# FPGA_PWR.net
KiCad netlist of a schematic drawn in Altium Designer
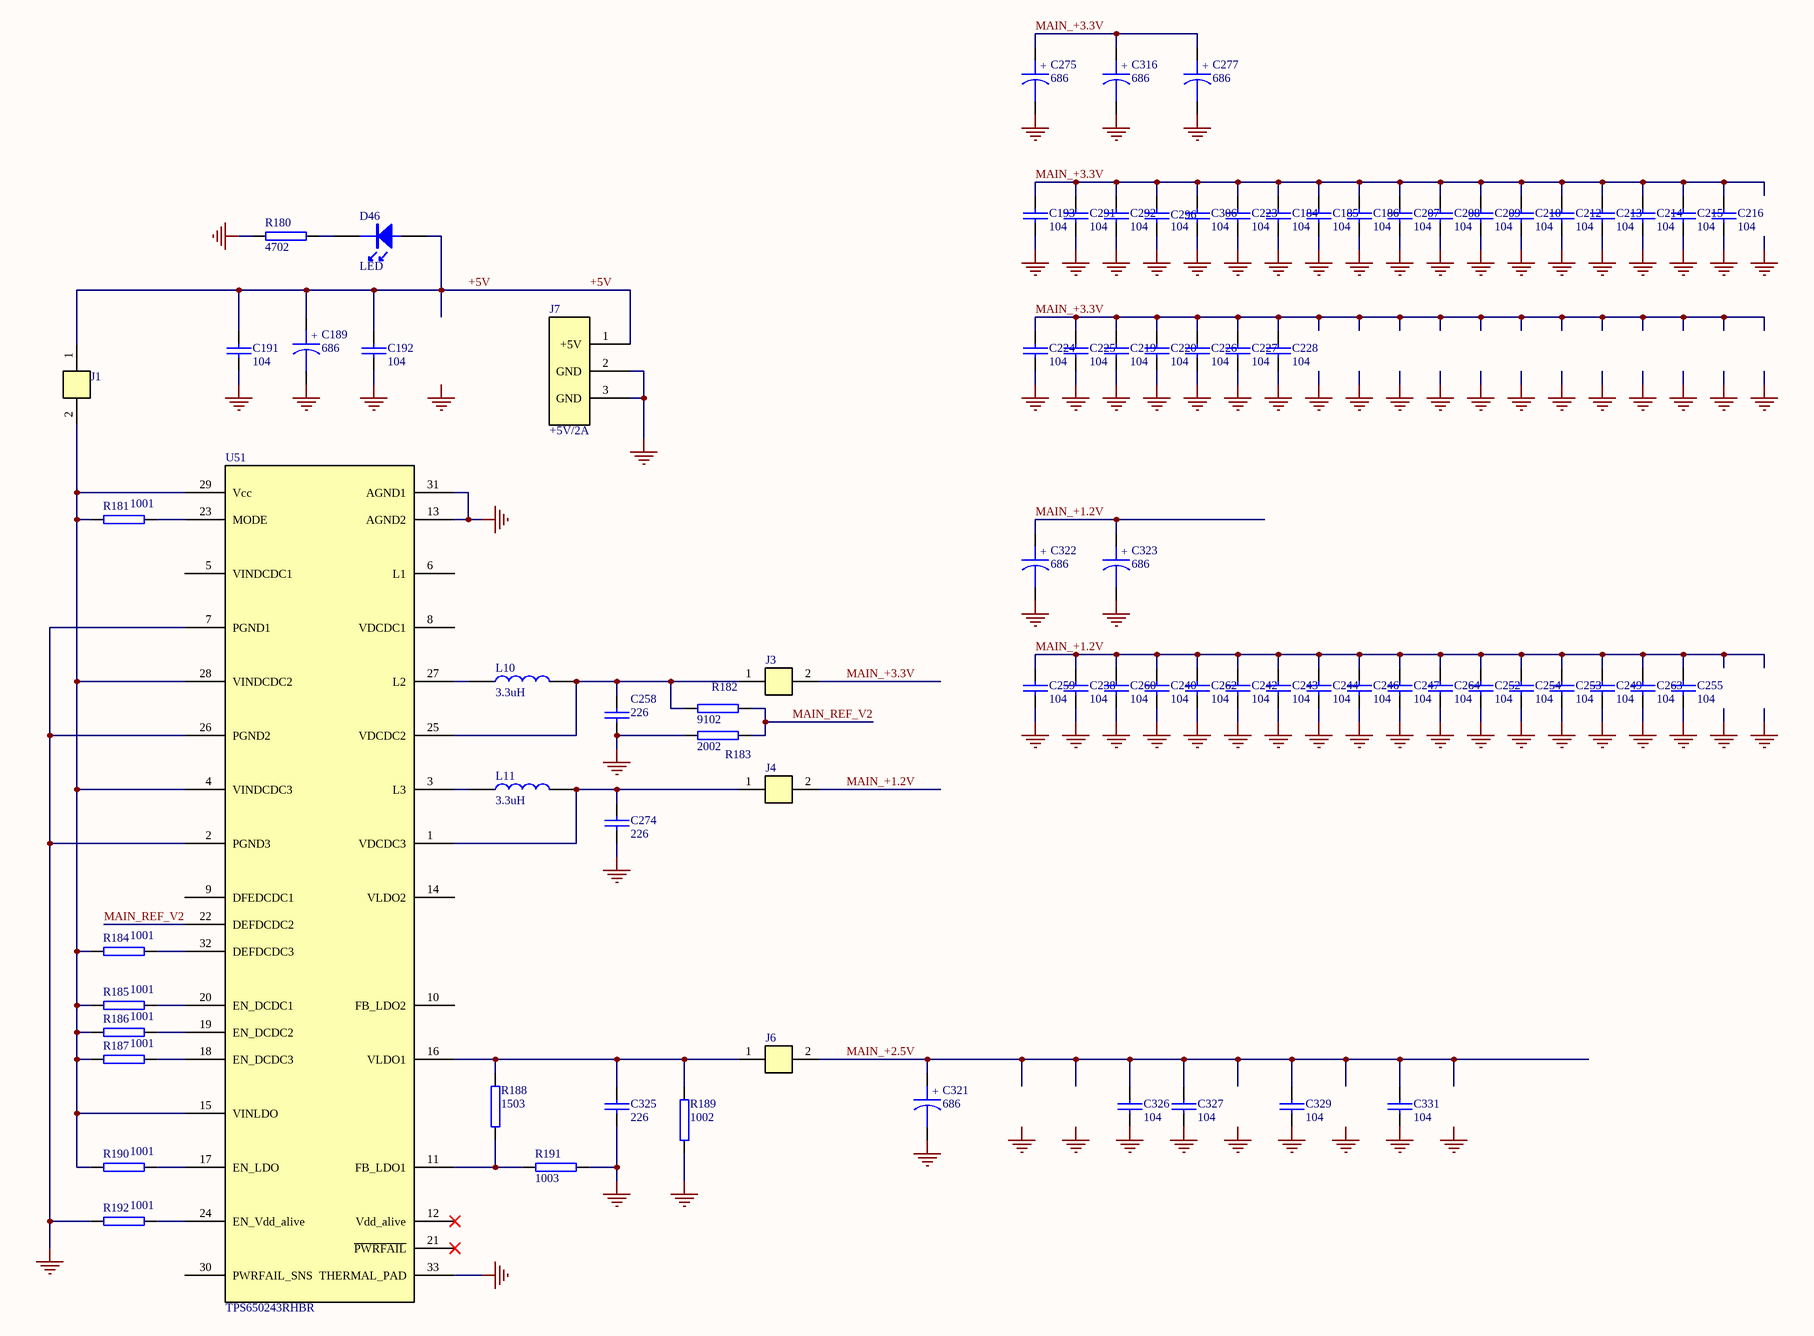
[diagram p0: FPGA_PWR.SchDoc]

(export (version "E")
  (design (tool "Eeschema 10.0.6"))
  (components
    (comp (ref "C184")
      (value "104")
      (footprint "0402C")
      (description "Capacitor")
      (libsource (lib "*") (part "CAP"))
    )
    (comp (ref "C185")
      (value "104")
      (footprint "0402C")
      (description "Capacitor")
      (libsource (lib "*") (part "CAP"))
    )
    (comp (ref "C186")
      (value "104")
      (footprint "0402C")
      (description "Capacitor")
      (libsource (lib "*") (part "CAP"))
    )
    (comp (ref "C189")
      (value "686")
      (footprint "6032")
      (description "Capacitor")
      (libsource (lib "*") (part "CAPACITOR POL"))
    )
    (comp (ref "C191")
      (value "104")
      (footprint "0805C")
      (description "Capacitor")
      (libsource (lib "*") (part "CAP"))
    )
    (comp (ref "C192")
      (value "104")
      (footprint "0805C")
      (description "Capacitor")
      (libsource (lib "*") (part "CAP"))
    )
    (comp (ref "C193")
      (value "104")
      (footprint "0805-104")
      (description "Capacitor")
      (libsource (lib "*") (part "CAP"))
    )
    (comp (ref "C207")
      (value "104")
      (footprint "0402C")
      (description "Capacitor")
      (libsource (lib "*") (part "CAP"))
    )
    (comp (ref "C208")
      (value "104")
      (footprint "0402C")
      (description "Capacitor")
      (libsource (lib "*") (part "CAP"))
    )
    (comp (ref "C209")
      (value "104")
      (footprint "0402C")
      (description "Capacitor")
      (libsource (lib "*") (part "CAP"))
    )
    (comp (ref "C210")
      (value "104")
      (footprint "0402C")
      (description "Capacitor")
      (libsource (lib "*") (part "CAP"))
    )
    (comp (ref "C212")
      (value "104")
      (footprint "0402C")
      (description "Capacitor")
      (libsource (lib "*") (part "CAP"))
    )
    (comp (ref "C213")
      (value "104")
      (footprint "0402C")
      (description "Capacitor")
      (libsource (lib "*") (part "CAP"))
    )
    (comp (ref "C214")
      (value "104")
      (footprint "0402C")
      (description "Capacitor")
      (libsource (lib "*") (part "CAP"))
    )
    (comp (ref "C215")
      (value "104")
      (footprint "0402C")
      (description "Capacitor")
      (libsource (lib "*") (part "CAP"))
    )
    (comp (ref "C216")
      (value "104")
      (footprint "0402C")
      (description "Capacitor")
      (libsource (lib "*") (part "CAP"))
    )
    (comp (ref "C219")
      (value "104")
      (footprint "0402C")
      (description "Capacitor")
      (libsource (lib "*") (part "CAP"))
    )
    (comp (ref "C220")
      (value "104")
      (footprint "0402C")
      (description "Capacitor")
      (libsource (lib "*") (part "CAP"))
    )
    (comp (ref "C223")
      (value "104")
      (footprint "0402C")
      (description "Capacitor")
      (libsource (lib "*") (part "CAP"))
    )
    (comp (ref "C224")
      (value "104")
      (footprint "0402C")
      (description "Capacitor")
      (libsource (lib "*") (part "CAP"))
    )
    (comp (ref "C225")
      (value "104")
      (footprint "0402C")
      (description "Capacitor")
      (libsource (lib "*") (part "CAP"))
    )
    (comp (ref "C226")
      (value "104")
      (footprint "0402C")
      (description "Capacitor")
      (libsource (lib "*") (part "CAP"))
    )
    (comp (ref "C227")
      (value "104")
      (footprint "0402C")
      (description "Capacitor")
      (libsource (lib "*") (part "CAP"))
    )
    (comp (ref "C228")
      (value "104")
      (footprint "0402C")
      (description "Capacitor")
      (libsource (lib "*") (part "CAP"))
    )
    (comp (ref "C238")
      (value "104")
      (footprint "0402C")
      (description "Capacitor")
      (libsource (lib "*") (part "CAP"))
    )
    (comp (ref "C240")
      (value "104")
      (footprint "0805-104")
      (description "Capacitor")
      (libsource (lib "*") (part "CAP"))
    )
    (comp (ref "C242")
      (value "104")
      (footprint "0402C")
      (description "Capacitor")
      (libsource (lib "*") (part "CAP"))
    )
    (comp (ref "C243")
      (value "104")
      (footprint "0402C")
      (description "Capacitor")
      (libsource (lib "*") (part "CAP"))
    )
    (comp (ref "C244")
      (value "104")
      (footprint "0402C")
      (description "Capacitor")
      (libsource (lib "*") (part "CAP"))
    )
    (comp (ref "C246")
      (value "104")
      (footprint "0402C")
      (description "Capacitor")
      (libsource (lib "*") (part "CAP"))
    )
    (comp (ref "C247")
      (value "104")
      (footprint "0402C")
      (description "Capacitor")
      (libsource (lib "*") (part "CAP"))
    )
    (comp (ref "C249")
      (value "104")
      (footprint "0402C")
      (description "Capacitor")
      (libsource (lib "*") (part "CAP"))
    )
    (comp (ref "C252")
      (value "104")
      (footprint "0402C")
      (description "Capacitor")
      (libsource (lib "*") (part "CAP"))
    )
    (comp (ref "C253")
      (value "104")
      (footprint "0402C")
      (description "Capacitor")
      (libsource (lib "*") (part "CAP"))
    )
    (comp (ref "C254")
      (value "104")
      (footprint "0402C")
      (description "Capacitor")
      (libsource (lib "*") (part "CAP"))
    )
    (comp (ref "C255")
      (value "104")
      (footprint "0805-104")
      (description "Capacitor")
      (libsource (lib "*") (part "CAP"))
    )
    (comp (ref "C258")
      (value "226")
      (footprint "C226")
      (description "Capacitor")
      (libsource (lib "*") (part "CAP"))
    )
    (comp (ref "C259")
      (value "104")
      (footprint "0402C")
      (description "Capacitor")
      (libsource (lib "*") (part "CAP"))
    )
    (comp (ref "C260")
      (value "104")
      (footprint "0402C")
      (description "Capacitor")
      (libsource (lib "*") (part "CAP"))
    )
    (comp (ref "C262")
      (value "104")
      (footprint "0402C")
      (description "Capacitor")
      (libsource (lib "*") (part "CAP"))
    )
    (comp (ref "C263")
      (value "104")
      (footprint "0402C")
      (description "Capacitor")
      (libsource (lib "*") (part "CAP"))
    )
    (comp (ref "C264")
      (value "104")
      (footprint "0402C")
      (description "Capacitor")
      (libsource (lib "*") (part "CAP"))
    )
    (comp (ref "C274")
      (value "226")
      (footprint "C226")
      (description "Capacitor")
      (libsource (lib "*") (part "CAP"))
    )
    (comp (ref "C275")
      (value "686")
      (footprint "6032")
      (description "Capacitor")
      (libsource (lib "*") (part "CAPACITOR POL"))
    )
    (comp (ref "C277")
      (value "686")
      (footprint "6032")
      (description "Capacitor")
      (libsource (lib "*") (part "CAPACITOR POL"))
    )
    (comp (ref "C291")
      (value "104")
      (footprint "0402C")
      (description "Capacitor")
      (libsource (lib "*") (part "CAP"))
    )
    (comp (ref "C292")
      (value "104")
      (footprint "0402C")
      (description "Capacitor")
      (libsource (lib "*") (part "CAP"))
    )
    (comp (ref "C296")
      (value "104")
      (footprint "0805C")
      (description "Capacitor")
      (libsource (lib "*") (part "CAP"))
    )
    (comp (ref "C306")
      (value "104")
      (footprint "0402C")
      (description "Capacitor")
      (libsource (lib "*") (part "CAP"))
    )
    (comp (ref "C316")
      (value "686")
      (footprint "6032")
      (description "Capacitor")
      (libsource (lib "*") (part "CAPACITOR POL"))
    )
    (comp (ref "C321")
      (value "686")
      (footprint "6032")
      (description "Capacitor")
      (libsource (lib "*") (part "CAPACITOR POL"))
    )
    (comp (ref "C322")
      (value "686")
      (footprint "6032")
      (description "Capacitor")
      (libsource (lib "*") (part "CAPACITOR POL"))
    )
    (comp (ref "C323")
      (value "686")
      (footprint "6032")
      (description "Capacitor")
      (libsource (lib "*") (part "CAPACITOR POL"))
    )
    (comp (ref "C325")
      (value "226")
      (footprint "C226")
      (description "Capacitor")
      (libsource (lib "*") (part "CAP"))
    )
    (comp (ref "C326")
      (value "104")
      (footprint "0402C")
      (description "Capacitor")
      (libsource (lib "*") (part "CAP"))
    )
    (comp (ref "C327")
      (value "104")
      (footprint "0402C")
      (description "Capacitor")
      (libsource (lib "*") (part "CAP"))
    )
    (comp (ref "C329")
      (value "104")
      (footprint "0402C")
      (description "Capacitor")
      (libsource (lib "*") (part "CAP"))
    )
    (comp (ref "C331")
      (value "104")
      (footprint "0402C")
      (description "Capacitor")
      (libsource (lib "*") (part "CAP"))
    )
    (comp (ref "D46") (value "LED") (footprint "0805_LED") (libsource (lib "*") (part "LED")))
    (comp (ref "J1") (value "~") (footprint "I_ON") (libsource (lib "") (part "I_ON_1")))
    (comp (ref "J3") (value "~") (footprint "I_ON") (libsource (lib "*") (part "I_ON")))
    (comp (ref "J4") (value "~") (footprint "I_ON") (libsource (lib "*") (part "I_ON")))
    (comp (ref "J6") (value "~") (footprint "I_ON") (libsource (lib "*") (part "I_ON")))
    (comp (ref "J7") (value "+5V/2A") (footprint "POW") (libsource (lib "*") (part "POW")))
    (comp (ref "L10") (value "3.3uH") (footprint "L3R3") (libsource (lib "*") (part "L")))
    (comp (ref "L11") (value "3.3uH") (footprint "L3R3") (libsource (lib "*") (part "L")))
    (comp (ref "R180") (value "4702") (footprint "0805R") (libsource (lib "*") (part "RES2")))
    (comp (ref "R181") (value "1001") (footprint "0805R") (libsource (lib "*") (part "RES2")))
    (comp (ref "R182") (value "9102") (footprint "0805") (libsource (lib "*") (part "RES2")))
    (comp (ref "R183") (value "2002") (footprint "0805") (libsource (lib "*") (part "RES2")))
    (comp (ref "R184") (value "1001") (footprint "0805") (libsource (lib "*") (part "RES2")))
    (comp (ref "R185") (value "1001") (footprint "0805") (libsource (lib "*") (part "RES2")))
    (comp (ref "R186") (value "1001") (footprint "0805") (libsource (lib "*") (part "RES2")))
    (comp (ref "R187") (value "1001") (footprint "0805") (libsource (lib "*") (part "RES2")))
    (comp (ref "R188") (value "1503") (footprint "0805") (libsource (lib "*") (part "RES2")))
    (comp (ref "R189") (value "1002") (footprint "0805") (libsource (lib "") (part "RES2_1")))
    (comp (ref "R190") (value "1001") (footprint "0805") (libsource (lib "*") (part "RES2")))
    (comp (ref "R191") (value "1003") (footprint "0805") (libsource (lib "*") (part "RES2")))
    (comp (ref "R192") (value "1001") (footprint "0805") (libsource (lib "*") (part "RES2")))
    (comp (ref "U51") (value "TPS650243RHBR") (footprint "VQFN32") (libsource (lib "*") (part "TPS650243")))
  )
  (nets
    (net (code "1") (name "/+5V") (class "Default")
      (node (ref "C189") (pin "1") (pinfunction "1_1") (pintype "passive"))
      (node (ref "C191") (pin "2") (pinfunction "2_2") (pintype "passive"))
      (node (ref "C192") (pin "2") (pinfunction "2_2") (pintype "passive"))
      (node (ref "D46") (pin "1") (pinfunction "A_1") (pintype "passive"))
      (node (ref "J1") (pin "1") (pintype "passive"))
      (node (ref "J7") (pin "1") (pinfunction "+5V_1") (pintype "passive"))
    )
    (net (code "2") (name "/MAIN_+1.2V") (class "Default")
      (node (ref "C238") (pin "2") (pinfunction "2_2") (pintype "passive"))
      (node (ref "C240") (pin "2") (pinfunction "2_2") (pintype "passive"))
      (node (ref "C242") (pin "2") (pinfunction "2_2") (pintype "passive"))
      (node (ref "C243") (pin "2") (pinfunction "2_2") (pintype "passive"))
      (node (ref "C244") (pin "2") (pinfunction "2_2") (pintype "passive"))
      (node (ref "C246") (pin "2") (pinfunction "2_2") (pintype "passive"))
      (node (ref "C247") (pin "2") (pinfunction "2_2") (pintype "passive"))
      (node (ref "C249") (pin "2") (pinfunction "2_2") (pintype "passive"))
      (node (ref "C252") (pin "2") (pinfunction "2_2") (pintype "passive"))
      (node (ref "C253") (pin "2") (pinfunction "2_2") (pintype "passive"))
      (node (ref "C254") (pin "2") (pinfunction "2_2") (pintype "passive"))
      (node (ref "C255") (pin "2") (pinfunction "2_2") (pintype "passive"))
      (node (ref "C259") (pin "2") (pinfunction "2_2") (pintype "passive"))
      (node (ref "C260") (pin "2") (pinfunction "2_2") (pintype "passive"))
      (node (ref "C262") (pin "2") (pinfunction "2_2") (pintype "passive"))
      (node (ref "C263") (pin "2") (pinfunction "2_2") (pintype "passive"))
      (node (ref "C264") (pin "2") (pinfunction "2_2") (pintype "passive"))
      (node (ref "C322") (pin "1") (pinfunction "1_1") (pintype "passive"))
      (node (ref "C323") (pin "1") (pinfunction "1_1") (pintype "passive"))
      (node (ref "J4") (pin "2") (pintype "passive"))
    )
    (net (code "3") (name "/MAIN_+2.5V") (class "Default")
      (node (ref "C321") (pin "1") (pinfunction "1_1") (pintype "passive"))
      (node (ref "C326") (pin "2") (pinfunction "2_2") (pintype "passive"))
      (node (ref "C327") (pin "2") (pinfunction "2_2") (pintype "passive"))
      (node (ref "C329") (pin "2") (pinfunction "2_2") (pintype "passive"))
      (node (ref "C331") (pin "2") (pinfunction "2_2") (pintype "passive"))
      (node (ref "J6") (pin "2") (pintype "passive"))
    )
    (net (code "4") (name "/MAIN_+3.3V") (class "Default")
      (node (ref "C184") (pin "2") (pinfunction "2_2") (pintype "passive"))
      (node (ref "C185") (pin "2") (pinfunction "2_2") (pintype "passive"))
      (node (ref "C186") (pin "2") (pinfunction "2_2") (pintype "passive"))
      (node (ref "C193") (pin "2") (pinfunction "2_2") (pintype "passive"))
      (node (ref "C207") (pin "2") (pinfunction "2_2") (pintype "passive"))
      (node (ref "C208") (pin "2") (pinfunction "2_2") (pintype "passive"))
      (node (ref "C209") (pin "2") (pinfunction "2_2") (pintype "passive"))
      (node (ref "C210") (pin "2") (pinfunction "2_2") (pintype "passive"))
      (node (ref "C212") (pin "2") (pinfunction "2_2") (pintype "passive"))
      (node (ref "C213") (pin "2") (pinfunction "2_2") (pintype "passive"))
      (node (ref "C214") (pin "2") (pinfunction "2_2") (pintype "passive"))
      (node (ref "C215") (pin "2") (pinfunction "2_2") (pintype "passive"))
      (node (ref "C216") (pin "2") (pinfunction "2_2") (pintype "passive"))
      (node (ref "C219") (pin "2") (pinfunction "2_2") (pintype "passive"))
      (node (ref "C220") (pin "2") (pinfunction "2_2") (pintype "passive"))
      (node (ref "C223") (pin "2") (pinfunction "2_2") (pintype "passive"))
      (node (ref "C224") (pin "2") (pinfunction "2_2") (pintype "passive"))
      (node (ref "C225") (pin "2") (pinfunction "2_2") (pintype "passive"))
      (node (ref "C226") (pin "2") (pinfunction "2_2") (pintype "passive"))
      (node (ref "C227") (pin "2") (pinfunction "2_2") (pintype "passive"))
      (node (ref "C228") (pin "2") (pinfunction "2_2") (pintype "passive"))
      (node (ref "C275") (pin "1") (pinfunction "1_1") (pintype "passive"))
      (node (ref "C277") (pin "1") (pinfunction "1_1") (pintype "passive"))
      (node (ref "C291") (pin "2") (pinfunction "2_2") (pintype "passive"))
      (node (ref "C292") (pin "2") (pinfunction "2_2") (pintype "passive"))
      (node (ref "C296") (pin "2") (pinfunction "2_2") (pintype "passive"))
      (node (ref "C306") (pin "2") (pinfunction "2_2") (pintype "passive"))
      (node (ref "C316") (pin "1") (pinfunction "1_1") (pintype "passive"))
      (node (ref "J3") (pin "2") (pintype "passive"))
    )
    (net (code "5") (name "/MAIN_REF_V2") (class "Default")
      (node (ref "R182") (pin "2") (pinfunction "2_2") (pintype "passive"))
      (node (ref "R183") (pin "1") (pinfunction "1_1") (pintype "passive"))
      (node (ref "U51") (pin "22") (pinfunction "DEFDCDC2_22") (pintype "passive"))
    )
    (net (code "6") (name "DGND") (class "Default")
      (node (ref "C184") (pin "1") (pinfunction "1_1") (pintype "passive"))
      (node (ref "C185") (pin "1") (pinfunction "1_1") (pintype "passive"))
      (node (ref "C186") (pin "1") (pinfunction "1_1") (pintype "passive"))
      (node (ref "C189") (pin "2") (pinfunction "2_2") (pintype "passive"))
      (node (ref "C191") (pin "1") (pinfunction "1_1") (pintype "passive"))
      (node (ref "C192") (pin "1") (pinfunction "1_1") (pintype "passive"))
      (node (ref "C193") (pin "1") (pinfunction "1_1") (pintype "passive"))
      (node (ref "C207") (pin "1") (pinfunction "1_1") (pintype "passive"))
      (node (ref "C208") (pin "1") (pinfunction "1_1") (pintype "passive"))
      (node (ref "C209") (pin "1") (pinfunction "1_1") (pintype "passive"))
      (node (ref "C210") (pin "1") (pinfunction "1_1") (pintype "passive"))
      (node (ref "C212") (pin "1") (pinfunction "1_1") (pintype "passive"))
      (node (ref "C213") (pin "1") (pinfunction "1_1") (pintype "passive"))
      (node (ref "C214") (pin "1") (pinfunction "1_1") (pintype "passive"))
      (node (ref "C215") (pin "1") (pinfunction "1_1") (pintype "passive"))
      (node (ref "C216") (pin "1") (pinfunction "1_1") (pintype "passive"))
      (node (ref "C219") (pin "1") (pinfunction "1_1") (pintype "passive"))
      (node (ref "C220") (pin "1") (pinfunction "1_1") (pintype "passive"))
      (node (ref "C223") (pin "1") (pinfunction "1_1") (pintype "passive"))
      (node (ref "C224") (pin "1") (pinfunction "1_1") (pintype "passive"))
      (node (ref "C225") (pin "1") (pinfunction "1_1") (pintype "passive"))
      (node (ref "C226") (pin "1") (pinfunction "1_1") (pintype "passive"))
      (node (ref "C227") (pin "1") (pinfunction "1_1") (pintype "passive"))
      (node (ref "C228") (pin "1") (pinfunction "1_1") (pintype "passive"))
      (node (ref "C238") (pin "1") (pinfunction "1_1") (pintype "passive"))
      (node (ref "C240") (pin "1") (pinfunction "1_1") (pintype "passive"))
      (node (ref "C242") (pin "1") (pinfunction "1_1") (pintype "passive"))
      (node (ref "C243") (pin "1") (pinfunction "1_1") (pintype "passive"))
      (node (ref "C244") (pin "1") (pinfunction "1_1") (pintype "passive"))
      (node (ref "C246") (pin "1") (pinfunction "1_1") (pintype "passive"))
      (node (ref "C247") (pin "1") (pinfunction "1_1") (pintype "passive"))
      (node (ref "C249") (pin "1") (pinfunction "1_1") (pintype "passive"))
      (node (ref "C252") (pin "1") (pinfunction "1_1") (pintype "passive"))
      (node (ref "C253") (pin "1") (pinfunction "1_1") (pintype "passive"))
      (node (ref "C254") (pin "1") (pinfunction "1_1") (pintype "passive"))
      (node (ref "C255") (pin "1") (pinfunction "1_1") (pintype "passive"))
      (node (ref "C258") (pin "2") (pinfunction "2_2") (pintype "passive"))
      (node (ref "C259") (pin "1") (pinfunction "1_1") (pintype "passive"))
      (node (ref "C260") (pin "1") (pinfunction "1_1") (pintype "passive"))
      (node (ref "C262") (pin "1") (pinfunction "1_1") (pintype "passive"))
      (node (ref "C263") (pin "1") (pinfunction "1_1") (pintype "passive"))
      (node (ref "C264") (pin "1") (pinfunction "1_1") (pintype "passive"))
      (node (ref "C274") (pin "2") (pinfunction "2_2") (pintype "passive"))
      (node (ref "C275") (pin "2") (pinfunction "2_2") (pintype "passive"))
      (node (ref "C277") (pin "2") (pinfunction "2_2") (pintype "passive"))
      (node (ref "C291") (pin "1") (pinfunction "1_1") (pintype "passive"))
      (node (ref "C292") (pin "1") (pinfunction "1_1") (pintype "passive"))
      (node (ref "C296") (pin "1") (pinfunction "1_1") (pintype "passive"))
      (node (ref "C306") (pin "1") (pinfunction "1_1") (pintype "passive"))
      (node (ref "C316") (pin "2") (pinfunction "2_2") (pintype "passive"))
      (node (ref "C321") (pin "2") (pinfunction "2_2") (pintype "passive"))
      (node (ref "C322") (pin "2") (pinfunction "2_2") (pintype "passive"))
      (node (ref "C323") (pin "2") (pinfunction "2_2") (pintype "passive"))
      (node (ref "C325") (pin "2") (pinfunction "2_2") (pintype "passive"))
      (node (ref "C326") (pin "1") (pinfunction "1_1") (pintype "passive"))
      (node (ref "C327") (pin "1") (pinfunction "1_1") (pintype "passive"))
      (node (ref "C329") (pin "1") (pinfunction "1_1") (pintype "passive"))
      (node (ref "C331") (pin "1") (pinfunction "1_1") (pintype "passive"))
      (node (ref "J7") (pin "2") (pinfunction "GND_2") (pintype "passive"))
      (node (ref "J7") (pin "3") (pinfunction "GND_3") (pintype "passive"))
      (node (ref "R180") (pin "1") (pinfunction "1_1") (pintype "passive"))
      (node (ref "R183") (pin "2") (pinfunction "2_2") (pintype "passive"))
      (node (ref "R189") (pin "2") (pinfunction "2_2") (pintype "passive"))
      (node (ref "R191") (pin "2") (pinfunction "2_2") (pintype "passive"))
      (node (ref "R192") (pin "1") (pinfunction "1_1") (pintype "passive"))
      (node (ref "U51") (pin "13") (pinfunction "AGND2_13") (pintype "passive"))
      (node (ref "U51") (pin "2") (pinfunction "PGND3_2") (pintype "passive"))
      (node (ref "U51") (pin "26") (pinfunction "PGND2_26") (pintype "passive"))
      (node (ref "U51") (pin "31") (pinfunction "AGND1_31") (pintype "passive"))
      (node (ref "U51") (pin "33") (pinfunction "THERMAL_PAD_33") (pintype "passive"))
      (node (ref "U51") (pin "7") (pinfunction "PGND1_7") (pintype "passive"))
    )
    (net (code "7") (name "Net-(D46-K)") (class "Default")
      (node (ref "D46") (pin "2") (pinfunction "K_2") (pintype "passive"))
      (node (ref "R180") (pin "2") (pinfunction "2_2") (pintype "passive"))
    )
    (net (code "8") (name "Net-(U51-DEFDCDC3)") (class "Default")
      (node (ref "R184") (pin "2") (pinfunction "2_2") (pintype "passive"))
      (node (ref "U51") (pin "32") (pinfunction "DEFDCDC3_32") (pintype "passive"))
    )
    (net (code "9") (name "Net-(U51-EN_DCDC1)") (class "Default")
      (node (ref "R185") (pin "2") (pinfunction "2_2") (pintype "passive"))
      (node (ref "U51") (pin "20") (pinfunction "EN_DCDC1_20") (pintype "passive"))
    )
    (net (code "10") (name "Net-(U51-EN_DCDC2)") (class "Default")
      (node (ref "R186") (pin "2") (pinfunction "2_2") (pintype "passive"))
      (node (ref "U51") (pin "19") (pinfunction "EN_DCDC2_19") (pintype "passive"))
    )
    (net (code "11") (name "Net-(U51-EN_DCDC3)") (class "Default")
      (node (ref "R187") (pin "2") (pinfunction "2_2") (pintype "passive"))
      (node (ref "U51") (pin "18") (pinfunction "EN_DCDC3_18") (pintype "passive"))
    )
    (net (code "12") (name "Net-(U51-EN_LDO)") (class "Default")
      (node (ref "R190") (pin "2") (pinfunction "2_2") (pintype "passive"))
      (node (ref "U51") (pin "17") (pinfunction "EN_LDO_17") (pintype "passive"))
    )
    (net (code "13") (name "Net-(U51-EN_Vdd_alive)") (class "Default")
      (node (ref "R192") (pin "2") (pinfunction "2_2") (pintype "passive"))
      (node (ref "U51") (pin "24") (pinfunction "EN_Vdd_alive_24") (pintype "passive"))
    )
    (net (code "14") (name "Net-(U51-FB_LDO1)") (class "Default")
      (node (ref "R188") (pin "1") (pinfunction "1_1") (pintype "passive"))
      (node (ref "R191") (pin "1") (pinfunction "1_1") (pintype "passive"))
      (node (ref "U51") (pin "11") (pinfunction "FB_LDO1_11") (pintype "passive"))
    )
    (net (code "15") (name "Net-(U51-L2)") (class "Default")
      (node (ref "L10") (pin "1") (pinfunction "1_1") (pintype "passive"))
      (node (ref "U51") (pin "27") (pinfunction "L2_27") (pintype "passive"))
    )
    (net (code "16") (name "Net-(U51-L3)") (class "Default")
      (node (ref "L11") (pin "1") (pinfunction "1_1") (pintype "passive"))
      (node (ref "U51") (pin "3") (pinfunction "L3_3") (pintype "passive"))
    )
    (net (code "17") (name "Net-(U51-MODE)") (class "Default")
      (node (ref "R181") (pin "2") (pinfunction "2_2") (pintype "passive"))
      (node (ref "U51") (pin "23") (pinfunction "MODE_23") (pintype "passive"))
    )
    (net (code "18") (name "Net-(U51-VDCDC2)") (class "Default")
      (node (ref "C258") (pin "1") (pinfunction "1_1") (pintype "passive"))
      (node (ref "J3") (pin "1") (pintype "passive"))
      (node (ref "L10") (pin "2") (pinfunction "2_2") (pintype "passive"))
      (node (ref "R182") (pin "1") (pinfunction "1_1") (pintype "passive"))
      (node (ref "U51") (pin "25") (pinfunction "VDCDC2_25") (pintype "passive"))
    )
    (net (code "19") (name "Net-(U51-VDCDC3)") (class "Default")
      (node (ref "C274") (pin "1") (pinfunction "1_1") (pintype "passive"))
      (node (ref "J4") (pin "1") (pintype "passive"))
      (node (ref "L11") (pin "2") (pinfunction "2_2") (pintype "passive"))
      (node (ref "U51") (pin "1") (pinfunction "VDCDC3_1") (pintype "passive"))
    )
    (net (code "20") (name "Net-(U51-VINDCDC2)") (class "Default")
      (node (ref "J1") (pin "2") (pintype "passive"))
      (node (ref "R181") (pin "1") (pinfunction "1_1") (pintype "passive"))
      (node (ref "R184") (pin "1") (pinfunction "1_1") (pintype "passive"))
      (node (ref "R185") (pin "1") (pinfunction "1_1") (pintype "passive"))
      (node (ref "R186") (pin "1") (pinfunction "1_1") (pintype "passive"))
      (node (ref "R187") (pin "1") (pinfunction "1_1") (pintype "passive"))
      (node (ref "R190") (pin "1") (pinfunction "1_1") (pintype "passive"))
      (node (ref "U51") (pin "15") (pinfunction "VINLDO_15") (pintype "passive"))
      (node (ref "U51") (pin "28") (pinfunction "VINDCDC2_28") (pintype "passive"))
      (node (ref "U51") (pin "29") (pinfunction "Vcc_29") (pintype "passive"))
      (node (ref "U51") (pin "4") (pinfunction "VINDCDC3_4") (pintype "passive"))
    )
    (net (code "21") (name "Net-(U51-VLDO1)") (class "Default")
      (node (ref "C325") (pin "1") (pinfunction "1_1") (pintype "passive"))
      (node (ref "J6") (pin "1") (pintype "passive"))
      (node (ref "R188") (pin "2") (pinfunction "2_2") (pintype "passive"))
      (node (ref "R189") (pin "1") (pinfunction "1_1") (pintype "passive"))
      (node (ref "U51") (pin "16") (pinfunction "VLDO1_16") (pintype "passive"))
    )
    (net (code "22") (name "unconnected-(U51-DFEDCDC1-Pad9)") (class "Default")
      (node (ref "U51") (pin "9") (pinfunction "DFEDCDC1_9") (pintype "passive"))
    )
    (net (code "23") (name "unconnected-(U51-FB_LDO2-Pad10)") (class "Default")
      (node (ref "U51") (pin "10") (pinfunction "FB_LDO2_10") (pintype "passive"))
    )
    (net (code "24") (name "unconnected-(U51-L1-Pad6)") (class "Default")
      (node (ref "U51") (pin "6") (pinfunction "L1_6") (pintype "passive"))
    )
    (net (code "25") (name "unconnected-(U51-PWRFAIL_SNS-Pad30)") (class "Default")
      (node (ref "U51") (pin "30") (pinfunction "PWRFAIL_SNS_30") (pintype "passive"))
    )
    (net (code "26") (name "unconnected-(U51-VDCDC1-Pad8)") (class "Default")
      (node (ref "U51") (pin "8") (pinfunction "VDCDC1_8") (pintype "passive"))
    )
    (net (code "27") (name "unconnected-(U51-VINDCDC1-Pad5)") (class "Default")
      (node (ref "U51") (pin "5") (pinfunction "VINDCDC1_5") (pintype "passive"))
    )
    (net (code "28") (name "unconnected-(U51-VLDO2-Pad14)") (class "Default")
      (node (ref "U51") (pin "14") (pinfunction "VLDO2_14") (pintype "passive"))
    )
    (net (code "29") (name "unconnected-(U51-Vdd_alive-Pad12)") (class "Default")
      (node (ref "U51") (pin "12") (pinfunction "Vdd_alive_12") (pintype "passive+no_connect"))
    )
    (net (code "30") (name "unconnected-(U51-~{PWRFAIL}-Pad21)") (class "Default")
      (node (ref "U51") (pin "21") (pinfunction "~{PWRFAIL}_21") (pintype "passive+no_connect"))
    )
  )
)
